# KMO_IO_MV2_9.net
KiCad netlist of a schematic drawn in EAGLE
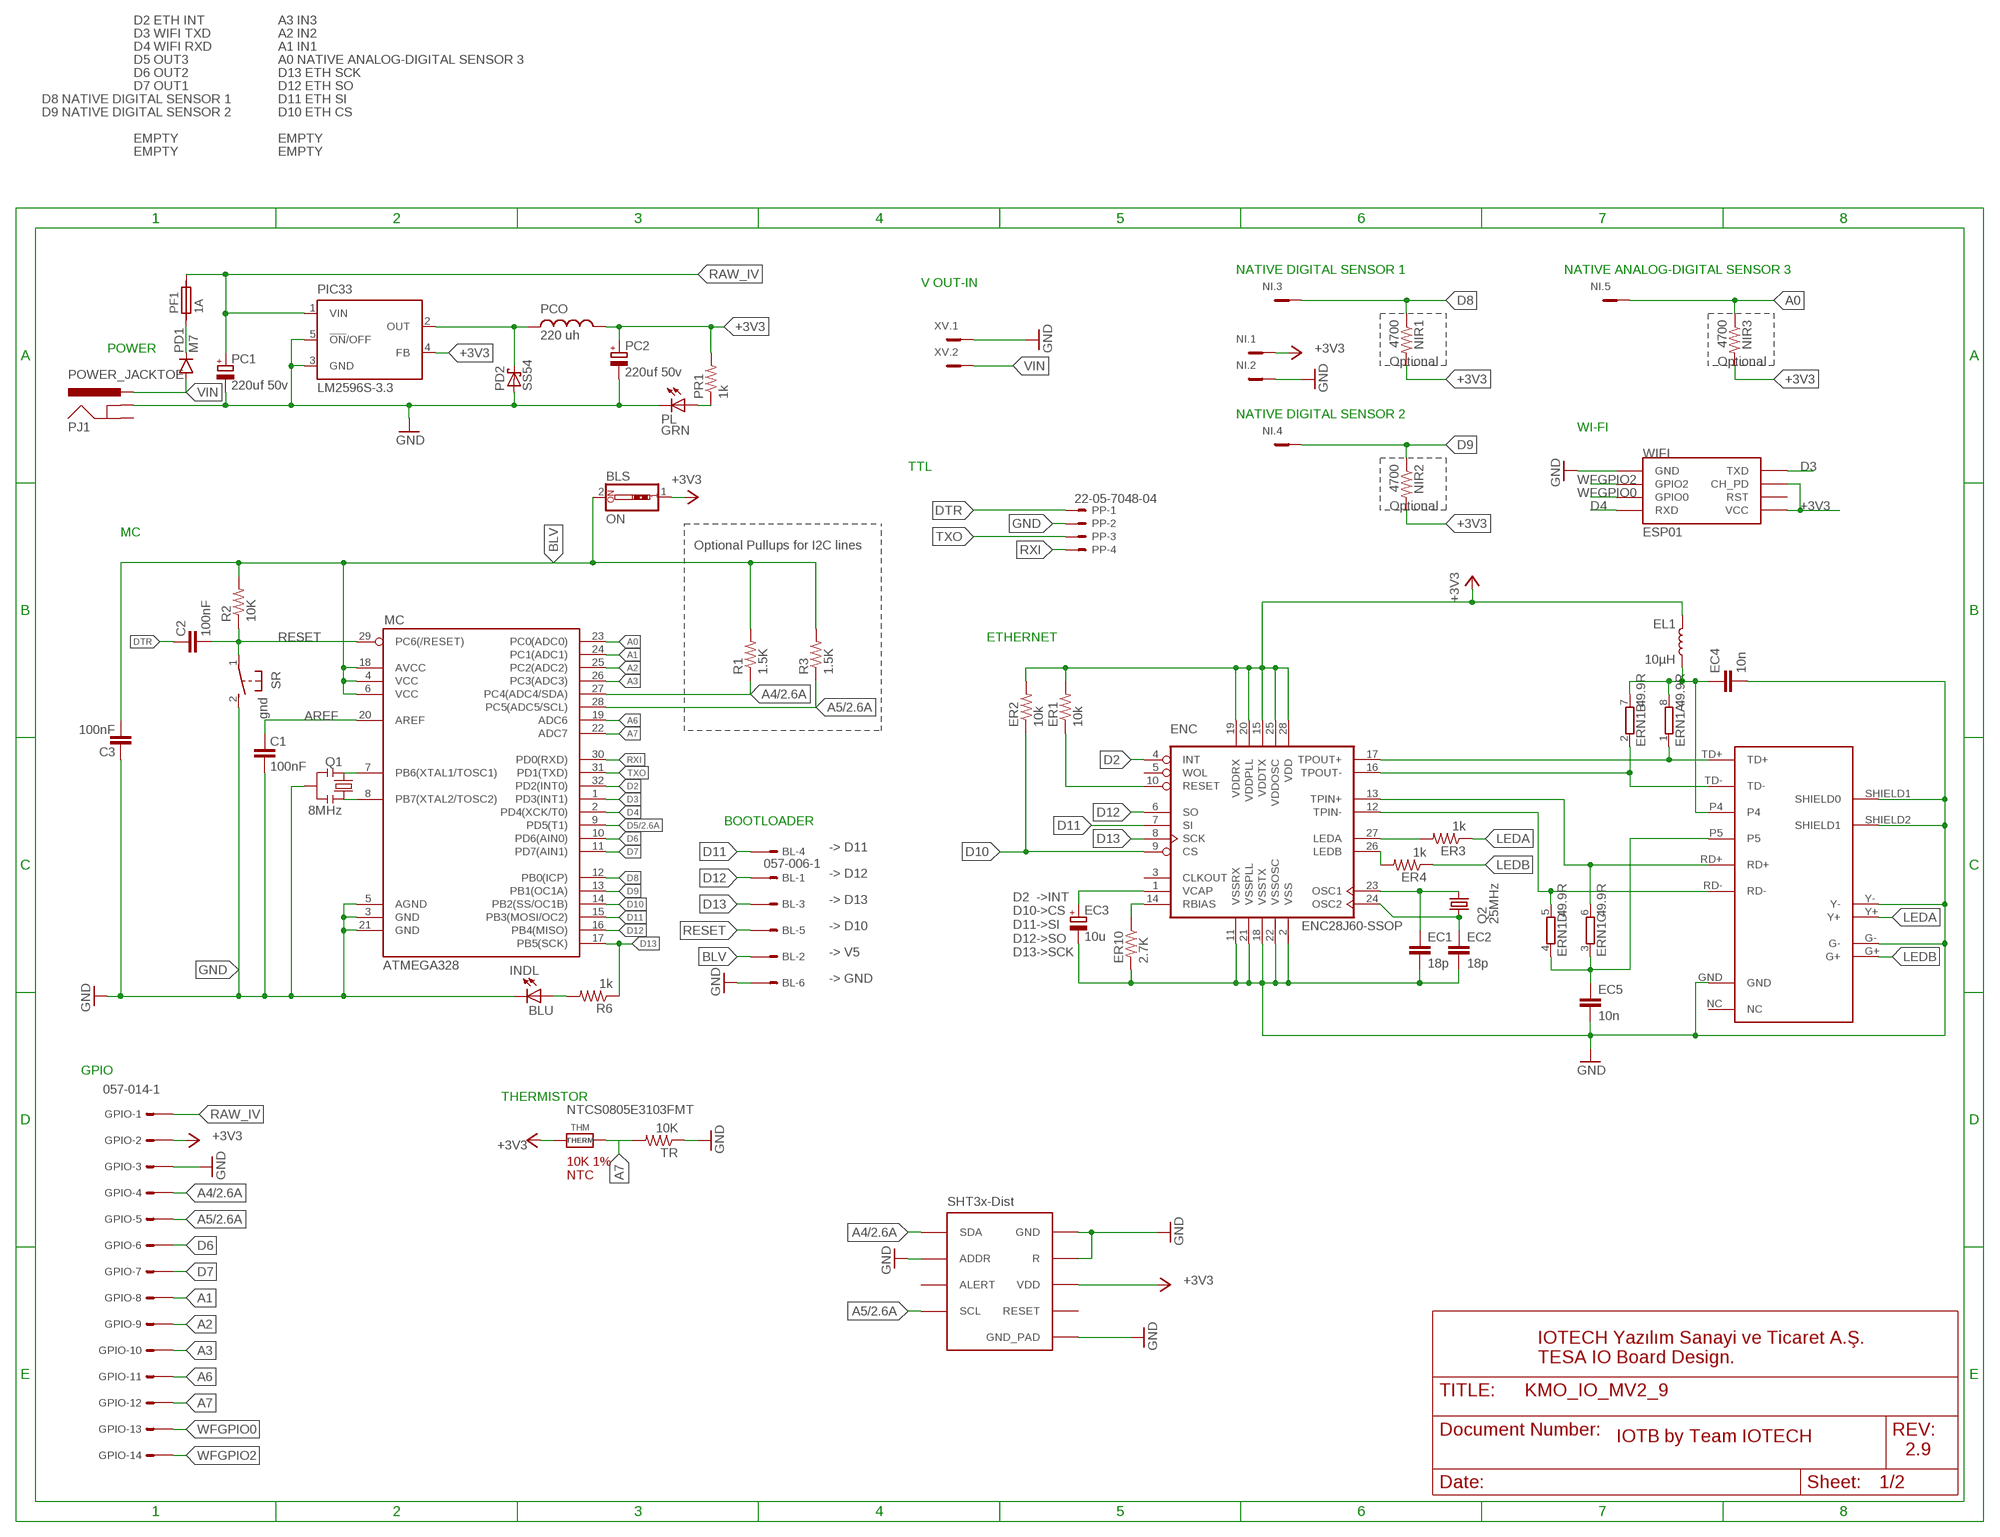
[diagram p0: schematic, sheet 1]
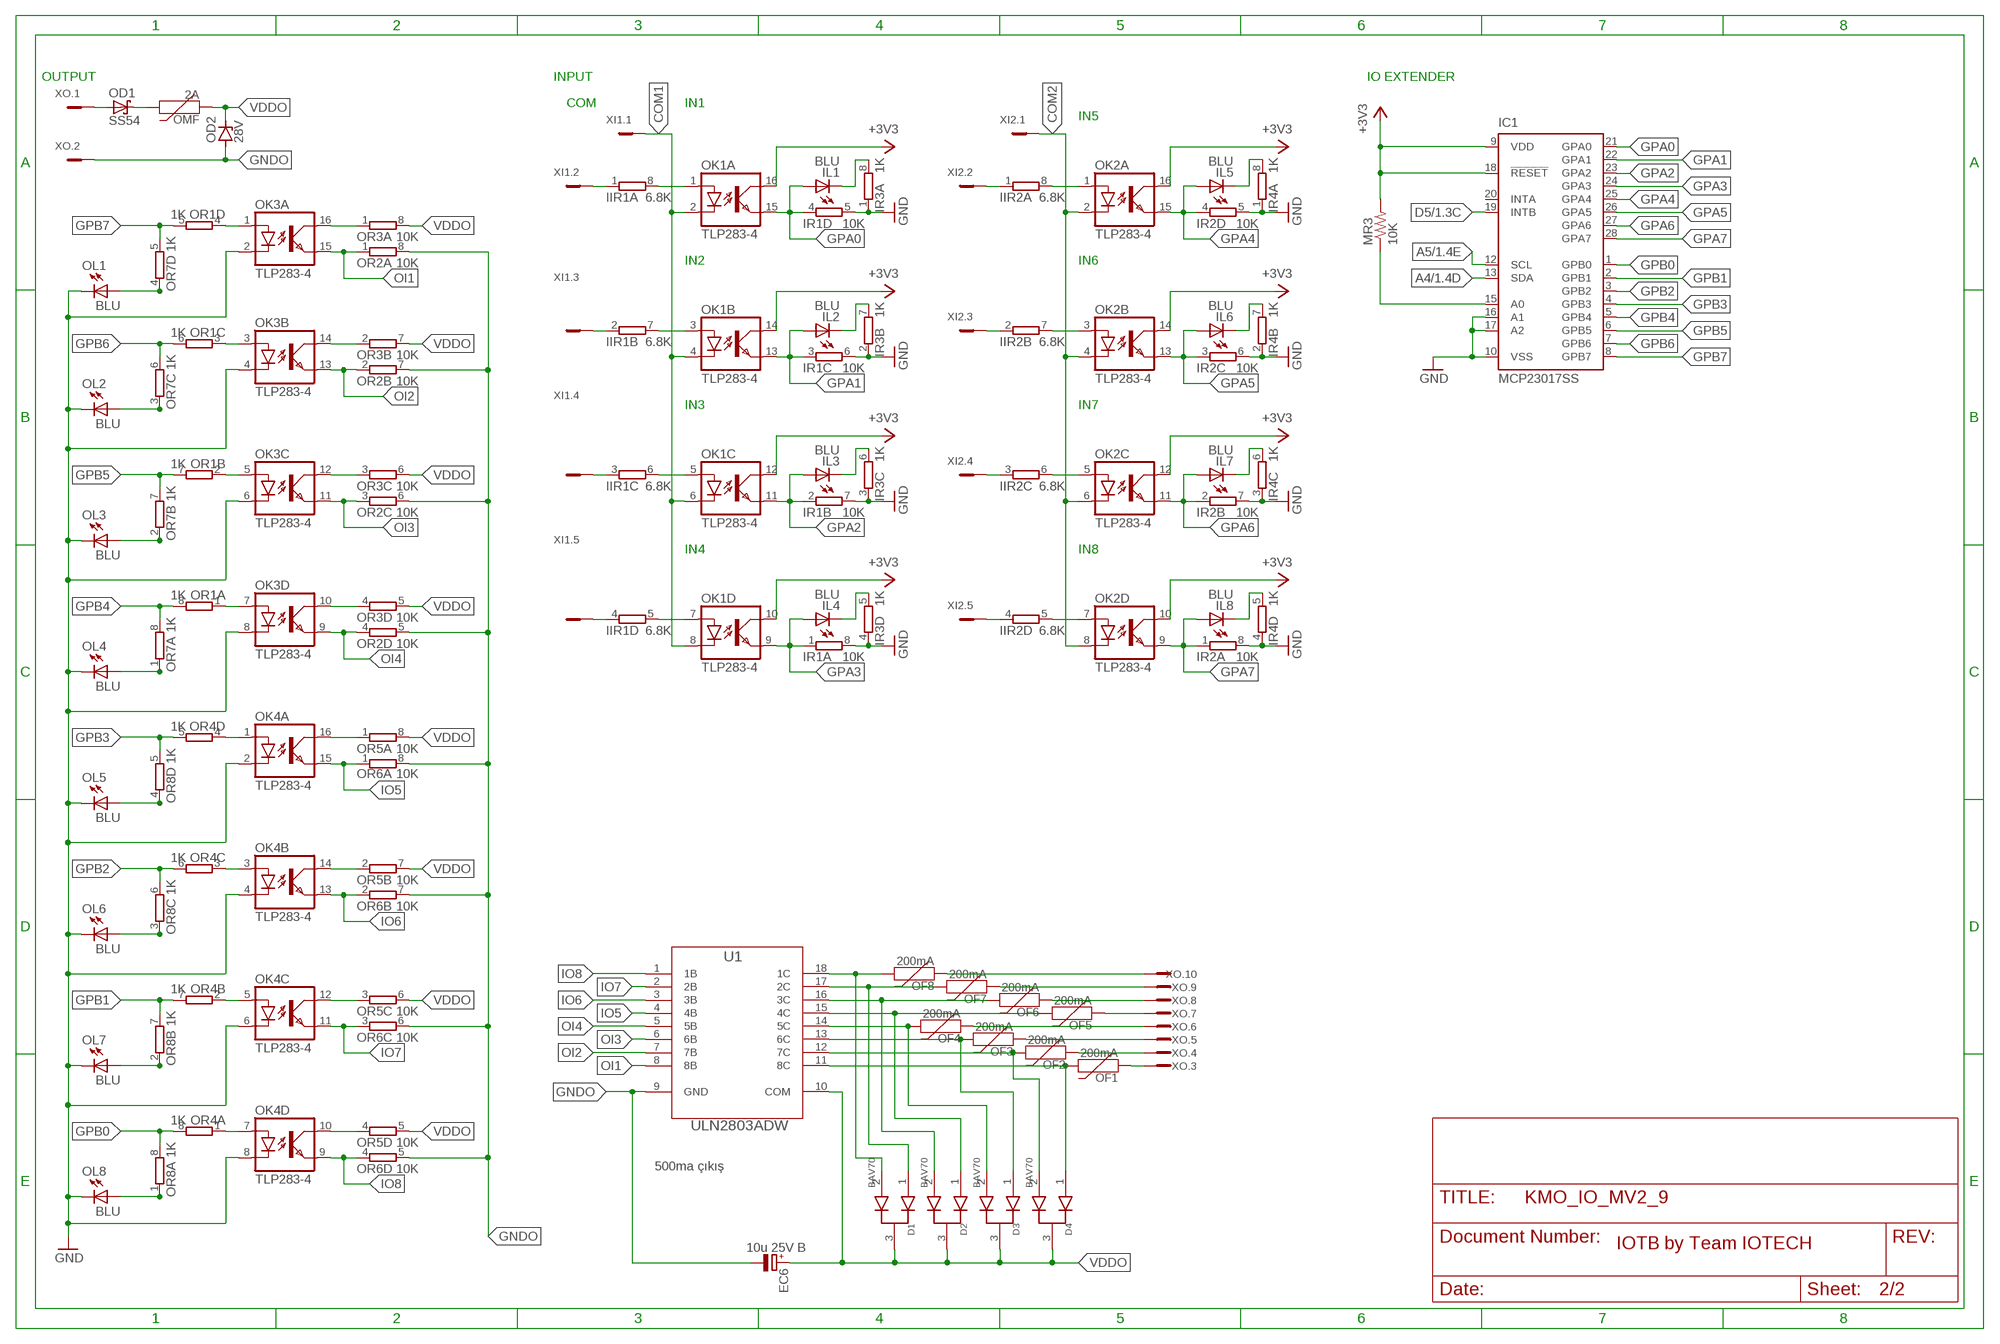
[diagram p1: schematic, sheet 2]

(export (version "E")
  (design (tool "Eeschema 10.0.6"))
  (components
    (comp (ref "D1")
      (value "BAV70")
      (footprint "eagle-import:SOT-23-3")
      (fields (field (name "MF") "Multicomp") (field (name "MP") "BAV70+"))
      (libsource (lib "eagle-import") (part "BAV70"))
    )
    (comp (ref "D2")
      (value "BAV70")
      (footprint "eagle-import:SOT-23-3")
      (fields (field (name "MF") "Multicomp") (field (name "MP") "BAV70+"))
      (libsource (lib "eagle-import") (part "BAV70"))
    )
    (comp (ref "D3")
      (value "BAV70")
      (footprint "eagle-import:SOT-23-3")
      (fields (field (name "MF") "Multicomp") (field (name "MP") "BAV70+"))
      (libsource (lib "eagle-import") (part "BAV70"))
    )
    (comp (ref "D4")
      (value "BAV70")
      (footprint "eagle-import:SOT-23-3")
      (fields (field (name "MF") "Multicomp") (field (name "MP") "BAV70+"))
      (libsource (lib "eagle-import") (part "BAV70"))
    )
    (comp (ref "EC6")
      (value "10u 25V B")
      (footprint "eagle-import:SMC_B")
      (libsource (lib "eagle-import") (part "CPOL-EUSMCB"))
    )
    (comp (ref "IC1")
      (value "MCP23017SS")
      (footprint "eagle-import:SSOP28")
      (fields (field (name "MF") "MICROCHIP") (field (name "MPN") "MCP23017-E/SS"))
      (libsource (lib "eagle-import") (part "MCP23017SS"))
    )
    (comp (ref "IIR1")
      (value "6.8K")
      (footprint "eagle-import:0603-ARV")
      (libsource (lib "eagle-import") (part "4R-N0603-ARV"))
    )
    (comp (ref "IIR2")
      (value "6.8K")
      (footprint "eagle-import:0603-ARV")
      (libsource (lib "eagle-import") (part "4R-N0603-ARV"))
    )
    (comp (ref "IL1")
      (value "BLU")
      (footprint "eagle-import:CHIP-LED0805")
      (libsource (lib "eagle-import") (part "LEDCHIP-LED0805"))
    )
    (comp (ref "IL2")
      (value "BLU")
      (footprint "eagle-import:CHIP-LED0805")
      (libsource (lib "eagle-import") (part "LEDCHIP-LED0805"))
    )
    (comp (ref "IL3")
      (value "BLU")
      (footprint "eagle-import:CHIP-LED0805")
      (libsource (lib "eagle-import") (part "LEDCHIP-LED0805"))
    )
    (comp (ref "IL4")
      (value "BLU")
      (footprint "eagle-import:CHIP-LED0805")
      (libsource (lib "eagle-import") (part "LEDCHIP-LED0805"))
    )
    (comp (ref "IL5")
      (value "BLU")
      (footprint "eagle-import:CHIP-LED0805")
      (libsource (lib "eagle-import") (part "LEDCHIP-LED0805"))
    )
    (comp (ref "IL6")
      (value "BLU")
      (footprint "eagle-import:CHIP-LED0805")
      (libsource (lib "eagle-import") (part "LEDCHIP-LED0805"))
    )
    (comp (ref "IL7")
      (value "BLU")
      (footprint "eagle-import:CHIP-LED0805")
      (libsource (lib "eagle-import") (part "LEDCHIP-LED0805"))
    )
    (comp (ref "IL8")
      (value "BLU")
      (footprint "eagle-import:CHIP-LED0805")
      (libsource (lib "eagle-import") (part "LEDCHIP-LED0805"))
    )
    (comp (ref "IR1")
      (value "10K")
      (footprint "eagle-import:0603-ARV")
      (libsource (lib "eagle-import") (part "4R-N0603-ARV"))
    )
    (comp (ref "IR2")
      (value "10K")
      (footprint "eagle-import:0603-ARV")
      (libsource (lib "eagle-import") (part "4R-N0603-ARV"))
    )
    (comp (ref "IR3")
      (value "1K")
      (footprint "eagle-import:0603-ARV")
      (libsource (lib "eagle-import") (part "4R-N0603-ARV"))
    )
    (comp (ref "IR4")
      (value "1K")
      (footprint "eagle-import:0603-ARV")
      (libsource (lib "eagle-import") (part "4R-N0603-ARV"))
    )
    (comp (ref "MR3")
      (value "10K")
      (footprint "eagle-import:0805")
      (libsource (lib "eagle-import") (part "RESISTOR0805-RES"))
    )
    (comp (ref "OD1")
      (value "SS54")
      (footprint "eagle-import:SMB")
      (libsource (lib "eagle-import") (part "SCHOTTKY-DIODESMD"))
    )
    (comp (ref "OD2")
      (value "28V")
      (footprint "eagle-import:SMB")
      (libsource (lib "eagle-import") (part "ZENER-DIODESMB"))
    )
    (comp (ref "OF1")
      (value "200mA")
      (footprint "eagle-import:1206")
      (libsource (lib "eagle-import") (part "PPTC_0.75A"))
    )
    (comp (ref "OF2")
      (value "200mA")
      (footprint "eagle-import:1206")
      (libsource (lib "eagle-import") (part "PPTC_0.75A"))
    )
    (comp (ref "OF3")
      (value "200mA")
      (footprint "eagle-import:1206")
      (libsource (lib "eagle-import") (part "PPTC_0.75A"))
    )
    (comp (ref "OF4")
      (value "200mA")
      (footprint "eagle-import:1206")
      (libsource (lib "eagle-import") (part "PPTC_0.75A"))
    )
    (comp (ref "OF5")
      (value "200mA")
      (footprint "eagle-import:1206")
      (libsource (lib "eagle-import") (part "PPTC_0.75A"))
    )
    (comp (ref "OF6")
      (value "200mA")
      (footprint "eagle-import:1206")
      (libsource (lib "eagle-import") (part "PPTC_0.75A"))
    )
    (comp (ref "OF7")
      (value "200mA")
      (footprint "eagle-import:1206")
      (libsource (lib "eagle-import") (part "PPTC_0.75A"))
    )
    (comp (ref "OF8")
      (value "200mA")
      (footprint "eagle-import:1206")
      (libsource (lib "eagle-import") (part "PPTC_0.75A"))
    )
    (comp (ref "OK1")
      (value "TLP283-4")
      (footprint "eagle-import:MINI-FLAT-16")
      (fields (field (name "SPICEPREFIX") "O"))
      (libsource (lib "eagle-import") (part "TLP283-4"))
    )
    (comp (ref "OK2")
      (value "TLP283-4")
      (footprint "eagle-import:MINI-FLAT-16")
      (fields (field (name "SPICEPREFIX") "O"))
      (libsource (lib "eagle-import") (part "TLP283-4"))
    )
    (comp (ref "OK3")
      (value "TLP283-4")
      (footprint "eagle-import:MINI-FLAT-16")
      (libsource (lib "eagle-import") (part "TLP283-4"))
    )
    (comp (ref "OK4")
      (value "TLP283-4")
      (footprint "eagle-import:MINI-FLAT-16")
      (libsource (lib "eagle-import") (part "TLP283-4"))
    )
    (comp (ref "OL1")
      (value "BLU")
      (footprint "eagle-import:CHIP-LED0805")
      (libsource (lib "eagle-import") (part "LEDCHIP-LED0805"))
    )
    (comp (ref "OL2")
      (value "BLU")
      (footprint "eagle-import:CHIP-LED0805")
      (libsource (lib "eagle-import") (part "LEDCHIP-LED0805"))
    )
    (comp (ref "OL3")
      (value "BLU")
      (footprint "eagle-import:CHIP-LED0805")
      (libsource (lib "eagle-import") (part "LEDCHIP-LED0805"))
    )
    (comp (ref "OL4")
      (value "BLU")
      (footprint "eagle-import:CHIP-LED0805")
      (libsource (lib "eagle-import") (part "LEDCHIP-LED0805"))
    )
    (comp (ref "OL5")
      (value "BLU")
      (footprint "eagle-import:CHIP-LED0805")
      (libsource (lib "eagle-import") (part "LEDCHIP-LED0805"))
    )
    (comp (ref "OL6")
      (value "BLU")
      (footprint "eagle-import:CHIP-LED0805")
      (libsource (lib "eagle-import") (part "LEDCHIP-LED0805"))
    )
    (comp (ref "OL7")
      (value "BLU")
      (footprint "eagle-import:CHIP-LED0805")
      (libsource (lib "eagle-import") (part "LEDCHIP-LED0805"))
    )
    (comp (ref "OL8")
      (value "BLU")
      (footprint "eagle-import:CHIP-LED0805")
      (libsource (lib "eagle-import") (part "LEDCHIP-LED0805"))
    )
    (comp (ref "OMF")
      (value "2A")
      (footprint "eagle-import:1206")
      (libsource (lib "eagle-import") (part "PPTC_0.75A"))
    )
    (comp (ref "OR1")
      (value "1K")
      (footprint "eagle-import:0603-ARV")
      (libsource (lib "eagle-import") (part "4R-N0603-ARV"))
    )
    (comp (ref "OR2")
      (value "10K")
      (footprint "eagle-import:0603-ARV")
      (libsource (lib "eagle-import") (part "4R-N0603-ARV"))
    )
    (comp (ref "OR3")
      (value "10K")
      (footprint "eagle-import:0603-ARV")
      (libsource (lib "eagle-import") (part "4R-N0603-ARV"))
    )
    (comp (ref "OR4")
      (value "1K")
      (footprint "eagle-import:0603-ARV")
      (libsource (lib "eagle-import") (part "4R-N0603-ARV"))
    )
    (comp (ref "OR5")
      (value "10K")
      (footprint "eagle-import:0603-ARV")
      (libsource (lib "eagle-import") (part "4R-N0603-ARV"))
    )
    (comp (ref "OR6")
      (value "10K")
      (footprint "eagle-import:0603-ARV")
      (libsource (lib "eagle-import") (part "4R-N0603-ARV"))
    )
    (comp (ref "OR7")
      (value "1K")
      (footprint "eagle-import:0603-ARV")
      (libsource (lib "eagle-import") (part "4R-N0603-ARV"))
    )
    (comp (ref "OR8")
      (value "1K")
      (footprint "eagle-import:0603-ARV")
      (libsource (lib "eagle-import") (part "4R-N0603-ARV"))
    )
    (comp (ref "U1")
      (value "ULN2803ADW")
      (footprint "eagle-import:SOIC127P1030X265-18N")
      (libsource (lib "eagle-import") (part "ULN2803ADW"))
    )
    (comp (ref "XI1")
      (value "MC5")
      (footprint "eagle-import:MC5")
      (libsource (lib "eagle-import") (part "MC5"))
    )
    (comp (ref "XI2")
      (value "MC5")
      (footprint "eagle-import:MC5")
      (libsource (lib "eagle-import") (part "MC5"))
    )
    (comp (ref "XO")
      (value "MC10")
      (footprint "eagle-import:MC10")
      (libsource (lib "eagle-import") (part "MC10"))
    )
    (comp (ref "BL")
      (value "057-006-1")
      (footprint "eagle-import:057-006-1")
      (libsource (lib "eagle-import") (part "057-006-1"))
    )
    (comp (ref "BLS")
      (value "ON")
      (footprint "eagle-import:EDG-01")
      (libsource (lib "eagle-import") (part "SW_DIP-1"))
    )
    (comp (ref "C1")
      (value "100nF")
      (footprint "eagle-import:0805")
      (libsource (lib "eagle-import") (part "CAP0805"))
    )
    (comp (ref "C2")
      (value "100nF")
      (footprint "eagle-import:0805")
      (libsource (lib "eagle-import") (part "CAP0805"))
    )
    (comp (ref "C3")
      (value "100nF")
      (footprint "eagle-import:0805")
      (libsource (lib "eagle-import") (part "CAP0805"))
    )
    (comp (ref "EC1")
      (value "18p")
      (footprint "eagle-import:0805")
      (libsource (lib "eagle-import") (part "CAP0805"))
    )
    (comp (ref "EC2")
      (value "18p")
      (footprint "eagle-import:0805")
      (libsource (lib "eagle-import") (part "CAP0805"))
    )
    (comp (ref "EC3")
      (value "10u")
      (footprint "eagle-import:CT3216")
      (libsource (lib "eagle-import") (part "CPOL-EUCT3216"))
    )
    (comp (ref "EC4")
      (value "10n")
      (footprint "eagle-import:0805")
      (libsource (lib "eagle-import") (part "CAP0805"))
    )
    (comp (ref "EC5")
      (value "10n")
      (footprint "eagle-import:0805")
      (libsource (lib "eagle-import") (part "CAP0805"))
    )
    (comp (ref "EL1")
      (value "10µH")
      (footprint "eagle-import:0805")
      (libsource (lib "eagle-import") (part "INDUCTOR-0805-3.3UH"))
    )
    (comp (ref "ENC")
      (value "ENC28J60-SSOP")
      (footprint "eagle-import:SSOP28")
      (libsource (lib "eagle-import") (part "ENC28J60-SSOP"))
    )
    (comp (ref "ER1")
      (value "10k")
      (footprint "eagle-import:0805")
      (libsource (lib "eagle-import") (part "RESISTOR0805-RES"))
    )
    (comp (ref "ER2")
      (value "10k")
      (footprint "eagle-import:0805")
      (libsource (lib "eagle-import") (part "RESISTOR0805-RES"))
    )
    (comp (ref "ER3")
      (value "1k")
      (footprint "eagle-import:0805")
      (libsource (lib "eagle-import") (part "RESISTOR0805-RES"))
    )
    (comp (ref "ER4")
      (value "1k")
      (footprint "eagle-import:0805")
      (libsource (lib "eagle-import") (part "RESISTOR0805-RES"))
    )
    (comp (ref "ER10")
      (value "2.7K")
      (footprint "eagle-import:0805")
      (libsource (lib "eagle-import") (part "RESISTOR0805-RES"))
    )
    (comp (ref "ERN1")
      (value "49.9R")
      (footprint "eagle-import:0603-ARV")
      (libsource (lib "eagle-import") (part "4R-N0603-ARV"))
    )
    (comp (ref "GPIO")
      (value "057-014-1")
      (footprint "eagle-import:057-014-1")
      (libsource (lib "eagle-import") (part "057-014-1"))
    )
    (comp (ref "INDL")
      (value "BLU")
      (footprint "eagle-import:CHIP-LED0805")
      (libsource (lib "eagle-import") (part "LEDCHIP-LED0805"))
    )
    (comp (ref "MC")
      (value "ATMEGA328")
      (footprint "eagle-import:TQFP32-08")
      (libsource (lib "eagle-import") (part "ATMEGA168"))
    )
    (comp (ref "NI")
      (value "MC5")
      (footprint "eagle-import:MC5")
      (libsource (lib "eagle-import") (part "MC5"))
    )
    (comp (ref "NIR1")
      (value "4700")
      (footprint "eagle-import:0805")
      (libsource (lib "eagle-import") (part "RESISTOR0805-RES"))
    )
    (comp (ref "NIR2")
      (value "4700")
      (footprint "eagle-import:0805")
      (libsource (lib "eagle-import") (part "RESISTOR0805-RES"))
    )
    (comp (ref "NIR3")
      (value "4700")
      (footprint "eagle-import:0805")
      (libsource (lib "eagle-import") (part "RESISTOR0805-RES"))
    )
    (comp (ref "PC1")
      (value "220uf 50v")
      (footprint "eagle-import:140CLH-1010")
      (libsource (lib "eagle-import") (part "CPOL-EU140CLH-1010"))
    )
    (comp (ref "PC2")
      (value "220uf 50v")
      (footprint "eagle-import:140CLH-1010")
      (libsource (lib "eagle-import") (part "CPOL-EU140CLH-1010"))
    )
    (comp (ref "PCO")
      (value "220 uh")
      (footprint "eagle-import:MSS1260")
      (libsource (lib "eagle-import") (part "MSS1260"))
    )
    (comp (ref "PD1")
      (value "M7")
      (footprint "eagle-import:SMA-DIODE")
      (libsource (lib "eagle-import") (part "DIODESMA"))
    )
    (comp (ref "PD2")
      (value "SS54")
      (footprint "eagle-import:SMB")
      (libsource (lib "eagle-import") (part "SCHOTTKY-DIODESMD"))
    )
    (comp (ref "PF1")
      (value "1A")
      (footprint "eagle-import:1820")
      (libsource (lib "eagle-import") (part "SIBA194600"))
    )
    (comp (ref "PIC33")
      (value "LM2596S-3.3")
      (footprint "eagle-import:TO263-5")
      (fields
        (field (name "MF") "NATIONAL SEMICONDUCTOR")
        (field (name "MPN") "LM2596S-ADJ/NOPB")
        (field (name "SPICEPREFIX") "X")
      )
      (libsource (lib "eagle-import") (part "LM2596S"))
    )
    (comp (ref "PJ1")
      (value "POWER_JACKTOE")
      (footprint "eagle-import:POWER_JACK_SMD_OVERPASTE_TOE")
      (libsource (lib "eagle-import") (part "POWER_JACKTOE"))
    )
    (comp (ref "PL")
      (value "GRN")
      (footprint "eagle-import:CHIP-LED0805")
      (libsource (lib "eagle-import") (part "LEDCHIP-LED0805"))
    )
    (comp (ref "PP")
      (value "22-05-7048-04")
      (footprint "eagle-import:7395-04")
      (fields (field (name "MF") "MOLEX"))
      (libsource (lib "eagle-import") (part "22-?-0405-7048"))
    )
    (comp (ref "PR1")
      (value "1k")
      (footprint "eagle-import:0805")
      (libsource (lib "eagle-import") (part "RESISTOR0805-RES"))
    )
    (comp (ref "Q1")
      (value "8MHz")
      (footprint "eagle-import:RESONATOR-SMD-1_1")
      (libsource (lib "eagle-import") (part "RESONATOR1{colon}1"))
    )
    (comp (ref "Q2")
      (value "25MHz")
      (footprint "eagle-import:5.0X3.2_2")
      (libsource (lib "eagle-import") (part "KX-9B"))
    )
    (comp (ref "R1")
      (value "1.5K")
      (footprint "eagle-import:0805")
      (libsource (lib "eagle-import") (part "RESISTOR0805-RES"))
    )
    (comp (ref "R2")
      (value "10K")
      (footprint "eagle-import:0805")
      (libsource (lib "eagle-import") (part "RESISTOR0805-RES"))
    )
    (comp (ref "R3")
      (value "1.5K")
      (footprint "eagle-import:0805")
      (libsource (lib "eagle-import") (part "RESISTOR0805-RES"))
    )
    (comp (ref "R6")
      (value "1k")
      (footprint "eagle-import:0805")
      (libsource (lib "eagle-import") (part "RESISTOR0805-RES"))
    )
    (comp (ref "SHT")
      (value "SHT3X")
      (footprint "eagle-import:SHT3X")
      (libsource (lib "eagle-import") (part "SHT3X"))
    )
    (comp (ref "SR")
      (value "gnd")
      (footprint "eagle-import:B3F-31XX")
      (fields (field (name "MPN") "B3F-3100"))
      (libsource (lib "eagle-import") (part "31-XX"))
    )
    (comp (ref "THM")
      (value "THERM")
      (footprint "eagle-import:MICROBUILDER_0805_NOTHERMALS")
      (libsource (lib "eagle-import") (part "MICROBUILDER_RESISTOR0805_NOTHERMALS"))
    )
    (comp (ref "TR")
      (value "10K")
      (footprint "eagle-import:0805")
      (libsource (lib "eagle-import") (part "RESISTOR0805-RES"))
    )
    (comp (ref "U$2")
      (value "HR911105A")
      (footprint "eagle-import:RJ45")
      (libsource (lib "eagle-import") (part "HR911105A"))
    )
    (comp (ref "WIFI")
      (value "ESP01")
      (footprint "eagle-import:ESP01")
      (libsource (lib "eagle-import") (part "ESP01"))
    )
    (comp (ref "XV")
      (value "MC2")
      (footprint "eagle-import:MC2")
      (libsource (lib "eagle-import") (part "MC2"))
    )
  )
  (nets
    (net (code "1") (name "+3V3") (class "Default")
      (node (ref "BLS") (pin "1") (pinfunction "1_1") (pintype "passive"))
      (node (ref "EL1") (pin "1") (pinfunction "1_1") (pintype "passive"))
      (node (ref "ENC") (pin "15") (pinfunction "VDDTX_15") (pintype "power_in"))
      (node (ref "ENC") (pin "19") (pinfunction "VDDRX_19") (pintype "power_in"))
      (node (ref "ENC") (pin "20") (pinfunction "VDDPLL_20") (pintype "power_in"))
      (node (ref "ENC") (pin "25") (pinfunction "VDDOSC_25") (pintype "power_in"))
      (node (ref "ENC") (pin "28") (pinfunction "VDD_28") (pintype "power_in"))
      (node (ref "ER1") (pin "2") (pinfunction "2_2") (pintype "passive"))
      (node (ref "ER2") (pin "2") (pinfunction "2_2") (pintype "passive"))
      (node (ref "GPIO") (pin "2") (pinfunction "S_2") (pintype "passive"))
      (node (ref "IC1") (pin "18") (pinfunction "~{RESET}_18") (pintype "input"))
      (node (ref "IC1") (pin "9") (pinfunction "VDD_9") (pintype "power_in"))
      (node (ref "MR3") (pin "2") (pinfunction "2_2") (pintype "passive"))
      (node (ref "NI") (pin "1") (pinfunction "SK_1") (pintype "passive"))
      (node (ref "NIR1") (pin "2") (pinfunction "2_2") (pintype "passive"))
      (node (ref "NIR2") (pin "2") (pinfunction "2_2") (pintype "passive"))
      (node (ref "NIR3") (pin "2") (pinfunction "2_2") (pintype "passive"))
      (node (ref "OK1") (pin "10") (pinfunction "COL_10") (pintype "passive"))
      (node (ref "OK1") (pin "12") (pinfunction "COL_12") (pintype "passive"))
      (node (ref "OK1") (pin "14") (pinfunction "COL_14") (pintype "passive"))
      (node (ref "OK1") (pin "16") (pinfunction "COL_16") (pintype "passive"))
      (node (ref "OK2") (pin "10") (pinfunction "COL_10") (pintype "passive"))
      (node (ref "OK2") (pin "12") (pinfunction "COL_12") (pintype "passive"))
      (node (ref "OK2") (pin "14") (pinfunction "COL_14") (pintype "passive"))
      (node (ref "OK2") (pin "16") (pinfunction "COL_16") (pintype "passive"))
      (node (ref "PC2") (pin "+") (pinfunction "+_+") (pintype "passive"))
      (node (ref "PCO") (pin "P$1") (pinfunction "P$1_P$1") (pintype "passive"))
      (node (ref "PIC33") (pin "4") (pinfunction "FB_4") (pintype "input"))
      (node (ref "PR1") (pin "2") (pinfunction "2_2") (pintype "passive"))
      (node (ref "SHT") (pin "VDD") (pinfunction "VDD_VDD") (pintype "bidirectional"))
      (node (ref "THM") (pin "1") (pinfunction "1_1") (pintype "passive"))
      (node (ref "WIFI") (pin "CH_PD") (pinfunction "CH_PD_CH_PD") (pintype "bidirectional"))
      (node (ref "WIFI") (pin "VCC") (pinfunction "VCC_VCC") (pintype "bidirectional"))
    )
    (net (code "2") (name "A0") (class "Default")
      (node (ref "MC") (pin "23") (pinfunction "PC0(ADC0)_23") (pintype "bidirectional"))
      (node (ref "NI") (pin "5") (pinfunction "SK_5") (pintype "passive"))
      (node (ref "NIR3") (pin "1") (pinfunction "1_1") (pintype "passive"))
    )
    (net (code "3") (name "A1") (class "Default")
      (node (ref "GPIO") (pin "8") (pinfunction "S_8") (pintype "passive"))
      (node (ref "MC") (pin "24") (pinfunction "PC1(ADC1)_24") (pintype "bidirectional"))
    )
    (net (code "4") (name "A2") (class "Default")
      (node (ref "GPIO") (pin "9") (pinfunction "S_9") (pintype "passive"))
      (node (ref "MC") (pin "25") (pinfunction "PC2(ADC2)_25") (pintype "bidirectional"))
    )
    (net (code "5") (name "A3") (class "Default")
      (node (ref "GPIO") (pin "10") (pinfunction "S_10") (pintype "passive"))
      (node (ref "MC") (pin "26") (pinfunction "PC3(ADC3)_26") (pintype "bidirectional"))
    )
    (net (code "6") (name "A4") (class "Default")
      (node (ref "GPIO") (pin "4") (pinfunction "S_4") (pintype "passive"))
      (node (ref "IC1") (pin "13") (pinfunction "SDA_13") (pintype "bidirectional"))
      (node (ref "MC") (pin "27") (pinfunction "PC4(ADC4/SDA)_27") (pintype "bidirectional"))
      (node (ref "R1") (pin "1") (pinfunction "1_1") (pintype "passive"))
      (node (ref "SHT") (pin "SDA") (pinfunction "SDA_SDA") (pintype "bidirectional"))
    )
    (net (code "7") (name "A5") (class "Default")
      (node (ref "GPIO") (pin "5") (pinfunction "S_5") (pintype "passive"))
      (node (ref "IC1") (pin "12") (pinfunction "SCL_12") (pintype "input"))
      (node (ref "MC") (pin "28") (pinfunction "PC5(ADC5/SCL)_28") (pintype "bidirectional"))
      (node (ref "R3") (pin "1") (pinfunction "1_1") (pintype "passive"))
      (node (ref "SHT") (pin "SCL") (pinfunction "SCL_SCL") (pintype "bidirectional"))
    )
    (net (code "8") (name "A6") (class "Default")
      (node (ref "GPIO") (pin "11") (pinfunction "S_11") (pintype "passive"))
      (node (ref "MC") (pin "19") (pinfunction "ADC6_19") (pintype "bidirectional"))
    )
    (net (code "9") (name "A7") (class "Default")
      (node (ref "GPIO") (pin "12") (pinfunction "S_12") (pintype "passive"))
      (node (ref "MC") (pin "22") (pinfunction "ADC7_22") (pintype "bidirectional"))
      (node (ref "THM") (pin "2") (pinfunction "2_2") (pintype "passive"))
      (node (ref "TR") (pin "2") (pinfunction "2_2") (pintype "passive"))
    )
    (net (code "10") (name "AREF") (class "Default")
      (node (ref "C1") (pin "2") (pinfunction "2_2") (pintype "passive"))
      (node (ref "MC") (pin "20") (pinfunction "AREF_20") (pintype "bidirectional"))
    )
    (net (code "11") (name "BLV") (class "Default")
      (node (ref "BL") (pin "2") (pinfunction "S_2") (pintype "passive"))
      (node (ref "BLS") (pin "2") (pinfunction "2_2") (pintype "passive"))
      (node (ref "C3") (pin "1") (pinfunction "1_1") (pintype "passive"))
      (node (ref "MC") (pin "18") (pinfunction "AVCC_18") (pintype "bidirectional"))
      (node (ref "MC") (pin "4") (pinfunction "VCC_4") (pintype "bidirectional"))
      (node (ref "MC") (pin "6") (pinfunction "VCC_6") (pintype "bidirectional"))
      (node (ref "R1") (pin "2") (pinfunction "2_2") (pintype "passive"))
      (node (ref "R2") (pin "2") (pinfunction "2_2") (pintype "passive"))
      (node (ref "R3") (pin "2") (pinfunction "2_2") (pintype "passive"))
    )
    (net (code "12") (name "COM1") (class "Default")
      (node (ref "OK1") (pin "2") (pinfunction "C_2") (pintype "passive"))
      (node (ref "OK1") (pin "4") (pinfunction "C_4") (pintype "passive"))
      (node (ref "OK1") (pin "6") (pinfunction "C_6") (pintype "passive"))
      (node (ref "OK1") (pin "8") (pinfunction "C_8") (pintype "passive"))
      (node (ref "XI1") (pin "1") (pinfunction "SK_1") (pintype "passive"))
    )
    (net (code "13") (name "COM2") (class "Default")
      (node (ref "OK2") (pin "2") (pinfunction "C_2") (pintype "passive"))
      (node (ref "OK2") (pin "4") (pinfunction "C_4") (pintype "passive"))
      (node (ref "OK2") (pin "6") (pinfunction "C_6") (pintype "passive"))
      (node (ref "OK2") (pin "8") (pinfunction "C_8") (pintype "passive"))
      (node (ref "XI2") (pin "1") (pinfunction "SK_1") (pintype "passive"))
    )
    (net (code "14") (name "D2") (class "Default")
      (node (ref "ENC") (pin "4") (pinfunction "INT_4") (pintype "output"))
      (node (ref "MC") (pin "32") (pinfunction "PD2(INT0)_32") (pintype "bidirectional"))
    )
    (net (code "15") (name "D3") (class "Default")
      (node (ref "MC") (pin "1") (pinfunction "PD3(INT1)_1") (pintype "bidirectional"))
      (node (ref "WIFI") (pin "TX") (pinfunction "TXD_TX") (pintype "bidirectional"))
    )
    (net (code "16") (name "D4") (class "Default")
      (node (ref "MC") (pin "2") (pinfunction "PD4(XCK/T0)_2") (pintype "bidirectional"))
      (node (ref "WIFI") (pin "RX") (pinfunction "RXD_RX") (pintype "bidirectional"))
    )
    (net (code "17") (name "D5") (class "Default")
      (node (ref "IC1") (pin "19") (pinfunction "INTB_19") (pintype "output"))
      (node (ref "MC") (pin "9") (pinfunction "PD5(T1)_9") (pintype "bidirectional"))
    )
    (net (code "18") (name "D6") (class "Default")
      (node (ref "GPIO") (pin "6") (pinfunction "S_6") (pintype "passive"))
      (node (ref "MC") (pin "10") (pinfunction "PD6(AIN0)_10") (pintype "bidirectional"))
    )
    (net (code "19") (name "D7") (class "Default")
      (node (ref "GPIO") (pin "7") (pinfunction "S_7") (pintype "passive"))
      (node (ref "MC") (pin "11") (pinfunction "PD7(AIN1)_11") (pintype "bidirectional"))
    )
    (net (code "20") (name "D8") (class "Default")
      (node (ref "MC") (pin "12") (pinfunction "PB0(ICP)_12") (pintype "bidirectional"))
      (node (ref "NI") (pin "3") (pinfunction "SK_3") (pintype "passive"))
      (node (ref "NIR1") (pin "1") (pinfunction "1_1") (pintype "passive"))
    )
    (net (code "21") (name "D9") (class "Default")
      (node (ref "MC") (pin "13") (pinfunction "PB1(OC1A)_13") (pintype "bidirectional"))
      (node (ref "NI") (pin "4") (pinfunction "SK_4") (pintype "passive"))
      (node (ref "NIR2") (pin "1") (pinfunction "1_1") (pintype "passive"))
    )
    (net (code "22") (name "D10") (class "Default")
      (node (ref "ENC") (pin "9") (pinfunction "CS_9") (pintype "input"))
      (node (ref "ER2") (pin "1") (pinfunction "1_1") (pintype "passive"))
      (node (ref "MC") (pin "14") (pinfunction "PB2(SS/OC1B)_14") (pintype "bidirectional"))
    )
    (net (code "23") (name "D11") (class "Default")
      (node (ref "BL") (pin "4") (pinfunction "S_4") (pintype "passive"))
      (node (ref "ENC") (pin "7") (pinfunction "SI_7") (pintype "input"))
      (node (ref "MC") (pin "15") (pinfunction "PB3(MOSI/OC2)_15") (pintype "bidirectional"))
    )
    (net (code "24") (name "D12") (class "Default")
      (node (ref "BL") (pin "1") (pinfunction "S_1") (pintype "passive"))
      (node (ref "ENC") (pin "6") (pinfunction "SO_6") (pintype "output"))
      (node (ref "MC") (pin "16") (pinfunction "PB4(MISO)_16") (pintype "bidirectional"))
    )
    (net (code "25") (name "D13") (class "Default")
      (node (ref "BL") (pin "3") (pinfunction "S_3") (pintype "passive"))
      (node (ref "ENC") (pin "8") (pinfunction "SCK_8") (pintype "input"))
      (node (ref "MC") (pin "17") (pinfunction "PB5(SCK)_17") (pintype "bidirectional"))
      (node (ref "R6") (pin "1") (pinfunction "1_1") (pintype "passive"))
    )
    (net (code "26") (name "DTR") (class "Default")
      (node (ref "C2") (pin "2") (pinfunction "2_2") (pintype "passive"))
      (node (ref "PP") (pin "1") (pinfunction "S_1") (pintype "passive"))
    )
    (net (code "27") (name "GND") (class "Default")
      (node (ref "BL") (pin "6") (pinfunction "S_6") (pintype "passive"))
      (node (ref "C1") (pin "1") (pinfunction "1_1") (pintype "passive"))
      (node (ref "C3") (pin "2") (pinfunction "2_2") (pintype "passive"))
      (node (ref "EC1") (pin "2") (pinfunction "2_2") (pintype "passive"))
      (node (ref "EC2") (pin "2") (pinfunction "2_2") (pintype "passive"))
      (node (ref "EC3") (pin "-") (pinfunction "-_-") (pintype "passive"))
      (node (ref "EC4") (pin "2") (pinfunction "2_2") (pintype "passive"))
      (node (ref "EC5") (pin "2") (pinfunction "2_2") (pintype "passive"))
      (node (ref "ENC") (pin "11") (pinfunction "VSSRX_11") (pintype "power_in"))
      (node (ref "ENC") (pin "18") (pinfunction "VSSTX_18") (pintype "power_in"))
      (node (ref "ENC") (pin "2") (pinfunction "VSS_2") (pintype "power_in"))
      (node (ref "ENC") (pin "21") (pinfunction "VSSPLL_21") (pintype "power_in"))
      (node (ref "ENC") (pin "22") (pinfunction "VSSOSC_22") (pintype "power_in"))
      (node (ref "ER10") (pin "2") (pinfunction "2_2") (pintype "passive"))
      (node (ref "GPIO") (pin "3") (pinfunction "S_3") (pintype "passive"))
      (node (ref "IC1") (pin "10") (pinfunction "VSS_10") (pintype "power_in"))
      (node (ref "IC1") (pin "16") (pinfunction "A1_16") (pintype "input"))
      (node (ref "IC1") (pin "17") (pinfunction "A2_17") (pintype "input"))
      (node (ref "INDL") (pin "C") (pinfunction "C_C") (pintype "passive"))
      (node (ref "IR1") (pin "5") (pinfunction "2_5") (pintype "passive"))
      (node (ref "IR1") (pin "6") (pinfunction "2_6") (pintype "passive"))
      (node (ref "IR1") (pin "7") (pinfunction "2_7") (pintype "passive"))
      (node (ref "IR1") (pin "8") (pinfunction "2_8") (pintype "passive"))
      (node (ref "IR2") (pin "5") (pinfunction "2_5") (pintype "passive"))
      (node (ref "IR2") (pin "6") (pinfunction "2_6") (pintype "passive"))
      (node (ref "IR2") (pin "7") (pinfunction "2_7") (pintype "passive"))
      (node (ref "IR2") (pin "8") (pinfunction "2_8") (pintype "passive"))
      (node (ref "IR3") (pin "1") (pinfunction "1_1") (pintype "passive"))
      (node (ref "IR3") (pin "2") (pinfunction "1_2") (pintype "passive"))
      (node (ref "IR3") (pin "3") (pinfunction "1_3") (pintype "passive"))
      (node (ref "IR3") (pin "4") (pinfunction "1_4") (pintype "passive"))
      (node (ref "IR4") (pin "1") (pinfunction "1_1") (pintype "passive"))
      (node (ref "IR4") (pin "2") (pinfunction "1_2") (pintype "passive"))
      (node (ref "IR4") (pin "3") (pinfunction "1_3") (pintype "passive"))
      (node (ref "IR4") (pin "4") (pinfunction "1_4") (pintype "passive"))
      (node (ref "MC") (pin "21") (pinfunction "GND_21") (pintype "bidirectional"))
      (node (ref "MC") (pin "3") (pinfunction "GND_3") (pintype "bidirectional"))
      (node (ref "MC") (pin "5") (pinfunction "AGND_5") (pintype "bidirectional"))
      (node (ref "NI") (pin "2") (pinfunction "SK_2") (pintype "passive"))
      (node (ref "OK3") (pin "2") (pinfunction "C_2") (pintype "passive"))
      (node (ref "OK3") (pin "4") (pinfunction "C_4") (pintype "passive"))
      (node (ref "OK3") (pin "6") (pinfunction "C_6") (pintype "passive"))
      (node (ref "OK3") (pin "8") (pinfunction "C_8") (pintype "passive"))
      (node (ref "OK4") (pin "2") (pinfunction "C_2") (pintype "passive"))
      (node (ref "OK4") (pin "4") (pinfunction "C_4") (pintype "passive"))
      (node (ref "OK4") (pin "6") (pinfunction "C_6") (pintype "passive"))
      (node (ref "OK4") (pin "8") (pinfunction "C_8") (pintype "passive"))
      (node (ref "OL1") (pin "C") (pinfunction "C_C") (pintype "passive"))
      (node (ref "OL2") (pin "C") (pinfunction "C_C") (pintype "passive"))
      (node (ref "OL3") (pin "C") (pinfunction "C_C") (pintype "passive"))
      (node (ref "OL4") (pin "C") (pinfunction "C_C") (pintype "passive"))
      (node (ref "OL5") (pin "C") (pinfunction "C_C") (pintype "passive"))
      (node (ref "OL6") (pin "C") (pinfunction "C_C") (pintype "passive"))
      (node (ref "OL7") (pin "C") (pinfunction "C_C") (pintype "passive"))
      (node (ref "OL8") (pin "C") (pinfunction "C_C") (pintype "passive"))
      (node (ref "PC1") (pin "-") (pinfunction "-_-") (pintype "passive"))
      (node (ref "PC2") (pin "-") (pinfunction "-_-") (pintype "passive"))
      (node (ref "PD2") (pin "A") (pinfunction "A_A") (pintype "passive"))
      (node (ref "PIC33") (pin "3") (pinfunction "GND_3") (pintype "power_in"))
      (node (ref "PIC33") (pin "5") (pinfunction "~{ON}/OFF_5") (pintype "input"))
      (node (ref "PJ1") (pin "GND") (pinfunction "GNDBREAK_GND") (pintype "bidirectional"))
      (node (ref "PL") (pin "C") (pinfunction "C_C") (pintype "passive"))
      (node (ref "PP") (pin "2") (pinfunction "S_2") (pintype "passive"))
      (node (ref "Q1") (pin "2") (pinfunction "2_2") (pintype "passive"))
      (node (ref "SHT") (pin "ADDR") (pinfunction "ADDR_ADDR") (pintype "bidirectional"))
      (node (ref "SHT") (pin "GND") (pinfunction "GND_GND") (pintype "bidirectional"))
      (node (ref "SHT") (pin "GND_PAD") (pinfunction "GND_PAD_GND_PAD") (pintype "bidirectional"))
      (node (ref "SHT") (pin "R") (pinfunction "R_R") (pintype "bidirectional"))
      (node (ref "SR") (pin "2") (pinfunction "S_2") (pintype "passive"))
      (node (ref "TR") (pin "1") (pinfunction "1_1") (pintype "passive"))
      (node (ref "U$2") (pin "G-") (pinfunction "G-_G-") (pintype "bidirectional"))
      (node (ref "U$2") (pin "GND") (pinfunction "GND_GND") (pintype "bidirectional"))
      (node (ref "U$2") (pin "SHIELD1") (pinfunction "SHIELD0_SHIELD1") (pintype "bidirectional"))
      (node (ref "U$2") (pin "SHIELD2") (pinfunction "SHIELD1_SHIELD2") (pintype "bidirectional"))
      (node (ref "U$2") (pin "Y-") (pinfunction "Y-_Y-") (pintype "bidirectional"))
      (node (ref "WIFI") (pin "GND") (pinfunction "GND_GND") (pintype "bidirectional"))
      (node (ref "XV") (pin "1") (pinfunction "SK_1") (pintype "passive"))
    )
    (net (code "28") (name "GNDO") (class "Default")
      (node (ref "EC6") (pin "-") (pinfunction "-_-") (pintype "passive"))
      (node (ref "OD2") (pin "A") (pinfunction "A_A") (pintype "passive"))
      (node (ref "OR2") (pin "5") (pinfunction "2_5") (pintype "passive"))
      (node (ref "OR2") (pin "6") (pinfunction "2_6") (pintype "passive"))
      (node (ref "OR2") (pin "7") (pinfunction "2_7") (pintype "passive"))
      (node (ref "OR2") (pin "8") (pinfunction "2_8") (pintype "passive"))
      (node (ref "OR6") (pin "5") (pinfunction "2_5") (pintype "passive"))
      (node (ref "OR6") (pin "6") (pinfunction "2_6") (pintype "passive"))
      (node (ref "OR6") (pin "7") (pinfunction "2_7") (pintype "passive"))
      (node (ref "OR6") (pin "8") (pinfunction "2_8") (pintype "passive"))
      (node (ref "U1") (pin "9") (pinfunction "GND_9") (pintype "passive"))
      (node (ref "XO") (pin "2") (pinfunction "SK_2") (pintype "passive"))
    )
    (net (code "29") (name "GPA0") (class "Default")
      (node (ref "IC1") (pin "21") (pinfunction "GPA0_21") (pintype "bidirectional"))
      (node (ref "IL1") (pin "A") (pinfunction "A_A") (pintype "passive"))
      (node (ref "IR1") (pin "4") (pinfunction "1_4") (pintype "passive"))
      (node (ref "OK1") (pin "15") (pinfunction "EMIT_15") (pintype "passive"))
    )
    (net (code "30") (name "GPA1") (class "Default")
      (node (ref "IC1") (pin "22") (pinfunction "GPA1_22") (pintype "bidirectional"))
      (node (ref "IL2") (pin "A") (pinfunction "A_A") (pintype "passive"))
      (node (ref "IR1") (pin "3") (pinfunction "1_3") (pintype "passive"))
      (node (ref "OK1") (pin "13") (pinfunction "EMIT_13") (pintype "passive"))
    )
    (net (code "31") (name "GPA2") (class "Default")
      (node (ref "IC1") (pin "23") (pinfunction "GPA2_23") (pintype "bidirectional"))
      (node (ref "IL3") (pin "A") (pinfunction "A_A") (pintype "passive"))
      (node (ref "IR1") (pin "2") (pinfunction "1_2") (pintype "passive"))
      (node (ref "OK1") (pin "11") (pinfunction "EMIT_11") (pintype "passive"))
    )
    (net (code "32") (name "GPA3") (class "Default")
      (node (ref "IC1") (pin "24") (pinfunction "GPA3_24") (pintype "bidirectional"))
      (node (ref "IL4") (pin "A") (pinfunction "A_A") (pintype "passive"))
      (node (ref "IR1") (pin "1") (pinfunction "1_1") (pintype "passive"))
      (node (ref "OK1") (pin "9") (pinfunction "EMIT_9") (pintype "passive"))
    )
    (net (code "33") (name "GPA4") (class "Default")
      (node (ref "IC1") (pin "25") (pinfunction "GPA4_25") (pintype "bidirectional"))
      (node (ref "IL5") (pin "A") (pinfunction "A_A") (pintype "passive"))
      (node (ref "IR2") (pin "4") (pinfunction "1_4") (pintype "passive"))
      (node (ref "OK2") (pin "15") (pinfunction "EMIT_15") (pintype "passive"))
    )
    (net (code "34") (name "GPA5") (class "Default")
      (node (ref "IC1") (pin "26") (pinfunction "GPA5_26") (pintype "bidirectional"))
      (node (ref "IL6") (pin "A") (pinfunction "A_A") (pintype "passive"))
      (node (ref "IR2") (pin "3") (pinfunction "1_3") (pintype "passive"))
      (node (ref "OK2") (pin "13") (pinfunction "EMIT_13") (pintype "passive"))
    )
    (net (code "35") (name "GPA6") (class "Default")
      (node (ref "IC1") (pin "27") (pinfunction "GPA6_27") (pintype "bidirectional"))
      (node (ref "IL7") (pin "A") (pinfunction "A_A") (pintype "passive"))
      (node (ref "IR2") (pin "2") (pinfunction "1_2") (pintype "passive"))
      (node (ref "OK2") (pin "11") (pinfunction "EMIT_11") (pintype "passive"))
    )
    (net (code "36") (name "GPA7") (class "Default")
      (node (ref "IC1") (pin "28") (pinfunction "GPA7_28") (pintype "bidirectional"))
      (node (ref "IL8") (pin "A") (pinfunction "A_A") (pintype "passive"))
      (node (ref "IR2") (pin "1") (pinfunction "1_1") (pintype "passive"))
      (node (ref "OK2") (pin "9") (pinfunction "EMIT_9") (pintype "passive"))
    )
    (net (code "37") (name "GPB0") (class "Default")
      (node (ref "IC1") (pin "1") (pinfunction "GPB0_1") (pintype "bidirectional"))
      (node (ref "OR4") (pin "8") (pinfunction "2_8") (pintype "passive"))
      (node (ref "OR8") (pin "8") (pinfunction "2_8") (pintype "passive"))
    )
    (net (code "38") (name "GPB1") (class "Default")
      (node (ref "IC1") (pin "2") (pinfunction "GPB1_2") (pintype "bidirectional"))
      (node (ref "OR4") (pin "7") (pinfunction "2_7") (pintype "passive"))
      (node (ref "OR8") (pin "7") (pinfunction "2_7") (pintype "passive"))
    )
    (net (code "39") (name "GPB2") (class "Default")
      (node (ref "IC1") (pin "3") (pinfunction "GPB2_3") (pintype "bidirectional"))
      (node (ref "OR4") (pin "6") (pinfunction "2_6") (pintype "passive"))
      (node (ref "OR8") (pin "6") (pinfunction "2_6") (pintype "passive"))
    )
    (net (code "40") (name "GPB3") (class "Default")
      (node (ref "IC1") (pin "4") (pinfunction "GPB3_4") (pintype "bidirectional"))
      (node (ref "OR4") (pin "5") (pinfunction "2_5") (pintype "passive"))
      (node (ref "OR8") (pin "5") (pinfunction "2_5") (pintype "passive"))
    )
    (net (code "41") (name "GPB4") (class "Default")
      (node (ref "IC1") (pin "5") (pinfunction "GPB4_5") (pintype "bidirectional"))
      (node (ref "OR1") (pin "8") (pinfunction "2_8") (pintype "passive"))
      (node (ref "OR7") (pin "8") (pinfunction "2_8") (pintype "passive"))
    )
    (net (code "42") (name "GPB5") (class "Default")
      (node (ref "IC1") (pin "6") (pinfunction "GPB5_6") (pintype "bidirectional"))
      (node (ref "OR1") (pin "7") (pinfunction "2_7") (pintype "passive"))
      (node (ref "OR7") (pin "7") (pinfunction "2_7") (pintype "passive"))
    )
    (net (code "43") (name "GPB6") (class "Default")
      (node (ref "IC1") (pin "7") (pinfunction "GPB6_7") (pintype "bidirectional"))
      (node (ref "OR1") (pin "6") (pinfunction "2_6") (pintype "passive"))
      (node (ref "OR7") (pin "6") (pinfunction "2_6") (pintype "passive"))
    )
    (net (code "44") (name "GPB7") (class "Default")
      (node (ref "IC1") (pin "8") (pinfunction "GPB7_8") (pintype "bidirectional"))
      (node (ref "OR1") (pin "5") (pinfunction "2_5") (pintype "passive"))
      (node (ref "OR7") (pin "5") (pinfunction "2_5") (pintype "passive"))
    )
    (net (code "45") (name "IO5") (class "Default")
      (node (ref "OK4") (pin "15") (pinfunction "EMIT_15") (pintype "passive"))
      (node (ref "OR6") (pin "1") (pinfunction "1_1") (pintype "passive"))
      (node (ref "U1") (pin "4") (pinfunction "4B_4") (pintype "input"))
    )
    (net (code "46") (name "IO6") (class "Default")
      (node (ref "OK4") (pin "13") (pinfunction "EMIT_13") (pintype "passive"))
      (node (ref "OR6") (pin "2") (pinfunction "1_2") (pintype "passive"))
      (node (ref "U1") (pin "3") (pinfunction "3B_3") (pintype "input"))
    )
    (net (code "47") (name "IO7") (class "Default")
      (node (ref "OK4") (pin "11") (pinfunction "EMIT_11") (pintype "passive"))
      (node (ref "OR6") (pin "3") (pinfunction "1_3") (pintype "passive"))
      (node (ref "U1") (pin "2") (pinfunction "2B_2") (pintype "input"))
    )
    (net (code "48") (name "IO8") (class "Default")
      (node (ref "OK4") (pin "9") (pinfunction "EMIT_9") (pintype "passive"))
      (node (ref "OR6") (pin "4") (pinfunction "1_4") (pintype "passive"))
      (node (ref "U1") (pin "1") (pinfunction "1B_1") (pintype "input"))
    )
    (net (code "49") (name "LEDA") (class "Default")
      (node (ref "ER3") (pin "1") (pinfunction "1_1") (pintype "passive"))
      (node (ref "U$2") (pin "Y+") (pinfunction "Y+_Y+") (pintype "bidirectional"))
    )
    (net (code "50") (name "LEDB") (class "Default")
      (node (ref "ER4") (pin "1") (pinfunction "1_1") (pintype "passive"))
      (node (ref "U$2") (pin "G+") (pinfunction "G+_G+") (pintype "bidirectional"))
    )
    (net (code "51") (name "Net-(ENC-LEDA)") (class "Default")
      (node (ref "ENC") (pin "27") (pinfunction "LEDA_27") (pintype "output"))
      (node (ref "ER3") (pin "2") (pinfunction "2_2") (pintype "passive"))
    )
    (net (code "52") (name "Net-(ENC-LEDB)") (class "Default")
      (node (ref "ENC") (pin "26") (pinfunction "LEDB_26") (pintype "output"))
      (node (ref "ER4") (pin "2") (pinfunction "2_2") (pintype "passive"))
    )
    (net (code "53") (name "Net-(ENC-OSC1)") (class "Default")
      (node (ref "EC1") (pin "1") (pinfunction "1_1") (pintype "passive"))
      (node (ref "ENC") (pin "23") (pinfunction "OSC1_23") (pintype "input"))
      (node (ref "Q2") (pin "2") (pinfunction "2_2") (pintype "passive"))
    )
    (net (code "54") (name "Net-(ENC-OSC2)") (class "Default")
      (node (ref "EC2") (pin "1") (pinfunction "1_1") (pintype "passive"))
      (node (ref "ENC") (pin "24") (pinfunction "OSC2_24") (pintype "output"))
      (node (ref "Q2") (pin "1") (pinfunction "1_1") (pintype "passive"))
    )
    (net (code "55") (name "Net-(ENC-RBIAS)") (class "Default")
      (node (ref "ENC") (pin "14") (pinfunction "RBIAS_14") (pintype "passive"))
      (node (ref "ER10") (pin "1") (pinfunction "1_1") (pintype "passive"))
    )
    (net (code "56") (name "Net-(ENC-RESET)") (class "Default")
      (node (ref "ENC") (pin "10") (pinfunction "RESET_10") (pintype "input"))
      (node (ref "ER1") (pin "1") (pinfunction "1_1") (pintype "passive"))
    )
    (net (code "57") (name "Net-(ENC-TPIN+)") (class "Default")
      (node (ref "ENC") (pin "13") (pinfunction "TPIN+_13") (pintype "input"))
      (node (ref "ERN1") (pin "6") (pinfunction "2_6") (pintype "passive"))
      (node (ref "U$2") (pin "RD+") (pinfunction "RD+_RD+") (pintype "bidirectional"))
    )
    (net (code "58") (name "Net-(ENC-TPIN-)") (class "Default")
      (node (ref "ENC") (pin "12") (pinfunction "TPIN-_12") (pintype "input"))
      (node (ref "ERN1") (pin "5") (pinfunction "2_5") (pintype "passive"))
      (node (ref "U$2") (pin "RD-") (pinfunction "RD-_RD-") (pintype "bidirectional"))
    )
    (net (code "59") (name "Net-(ENC-TPOUT+)") (class "Default")
      (node (ref "ENC") (pin "17") (pinfunction "TPOUT+_17") (pintype "output"))
      (node (ref "ERN1") (pin "1") (pinfunction "1_1") (pintype "passive"))
      (node (ref "U$2") (pin "TD+") (pinfunction "TD+_TD+") (pintype "bidirectional"))
    )
    (net (code "60") (name "Net-(ENC-TPOUT-)") (class "Default")
      (node (ref "ENC") (pin "16") (pinfunction "TPOUT-_16") (pintype "output"))
      (node (ref "ERN1") (pin "2") (pinfunction "1_2") (pintype "passive"))
      (node (ref "U$2") (pin "TD-") (pinfunction "TD-_TD-") (pintype "bidirectional"))
    )
    (net (code "61") (name "Net-(ENC-VCAP)") (class "Default")
      (node (ref "EC3") (pin "+") (pinfunction "+_+") (pintype "passive"))
      (node (ref "ENC") (pin "1") (pinfunction "VCAP_1") (pintype "power_in"))
    )
    (net (code "62") (name "Net-(ERN1A-2)") (class "Default")
      (node (ref "EC4") (pin "1") (pinfunction "1_1") (pintype "passive"))
      (node (ref "EL1") (pin "2") (pinfunction "2_2") (pintype "passive"))
      (node (ref "ERN1") (pin "7") (pinfunction "2_7") (pintype "passive"))
      (node (ref "ERN1") (pin "8") (pinfunction "2_8") (pintype "passive"))
      (node (ref "U$2") (pin "P4") (pinfunction "P4_P4") (pintype "bidirectional"))
    )
    (net (code "63") (name "Net-(ERN1C-1)") (class "Default")
      (node (ref "EC5") (pin "1") (pinfunction "1_1") (pintype "passive"))
      (node (ref "ERN1") (pin "3") (pinfunction "1_3") (pintype "passive"))
      (node (ref "ERN1") (pin "4") (pinfunction "1_4") (pintype "passive"))
      (node (ref "U$2") (pin "P5") (pinfunction "P5_P5") (pintype "bidirectional"))
    )
    (net (code "64") (name "Net-(IC1-A0)") (class "Default")
      (node (ref "IC1") (pin "15") (pinfunction "A0_15") (pintype "input"))
      (node (ref "MR3") (pin "1") (pinfunction "1_1") (pintype "passive"))
    )
    (net (code "65") (name "Net-(IIR1A-2)") (class "Default")
      (node (ref "IIR1") (pin "8") (pinfunction "2_8") (pintype "passive"))
      (node (ref "OK1") (pin "1") (pinfunction "A_1") (pintype "passive"))
    )
    (net (code "66") (name "Net-(IIR1B-1)") (class "Default")
      (node (ref "IIR1") (pin "2") (pinfunction "1_2") (pintype "passive"))
      (node (ref "XI1") (pin "3") (pinfunction "SK_3") (pintype "passive"))
    )
    (net (code "67") (name "Net-(IIR1B-2)") (class "Default")
      (node (ref "IIR1") (pin "7") (pinfunction "2_7") (pintype "passive"))
      (node (ref "OK1") (pin "3") (pinfunction "A_3") (pintype "passive"))
    )
    (net (code "68") (name "Net-(IIR1C-1)") (class "Default")
      (node (ref "IIR1") (pin "3") (pinfunction "1_3") (pintype "passive"))
      (node (ref "XI1") (pin "4") (pinfunction "SK_4") (pintype "passive"))
    )
    (net (code "69") (name "Net-(IIR1C-2)") (class "Default")
      (node (ref "IIR1") (pin "6") (pinfunction "2_6") (pintype "passive"))
      (node (ref "OK1") (pin "5") (pinfunction "A_5") (pintype "passive"))
    )
    (net (code "70") (name "Net-(IIR1D-1)") (class "Default")
      (node (ref "IIR1") (pin "4") (pinfunction "1_4") (pintype "passive"))
      (node (ref "XI1") (pin "5") (pinfunction "SK_5") (pintype "passive"))
    )
    (net (code "71") (name "Net-(IIR1D-2)") (class "Default")
      (node (ref "IIR1") (pin "5") (pinfunction "2_5") (pintype "passive"))
      (node (ref "OK1") (pin "7") (pinfunction "A_7") (pintype "passive"))
    )
    (net (code "72") (name "Net-(IIR2A-2)") (class "Default")
      (node (ref "IIR2") (pin "8") (pinfunction "2_8") (pintype "passive"))
      (node (ref "OK2") (pin "1") (pinfunction "A_1") (pintype "passive"))
    )
    (net (code "73") (name "Net-(IIR2B-1)") (class "Default")
      (node (ref "IIR2") (pin "2") (pinfunction "1_2") (pintype "passive"))
      (node (ref "XI2") (pin "3") (pinfunction "SK_3") (pintype "passive"))
    )
    (net (code "74") (name "Net-(IIR2B-2)") (class "Default")
      (node (ref "IIR2") (pin "7") (pinfunction "2_7") (pintype "passive"))
      (node (ref "OK2") (pin "3") (pinfunction "A_3") (pintype "passive"))
    )
    (net (code "75") (name "Net-(IIR2C-1)") (class "Default")
      (node (ref "IIR2") (pin "3") (pinfunction "1_3") (pintype "passive"))
      (node (ref "XI2") (pin "4") (pinfunction "SK_4") (pintype "passive"))
    )
    (net (code "76") (name "Net-(IIR2C-2)") (class "Default")
      (node (ref "IIR2") (pin "6") (pinfunction "2_6") (pintype "passive"))
      (node (ref "OK2") (pin "5") (pinfunction "A_5") (pintype "passive"))
    )
    (net (code "77") (name "Net-(IIR2D-1)") (class "Default")
      (node (ref "IIR2") (pin "4") (pinfunction "1_4") (pintype "passive"))
      (node (ref "XI2") (pin "5") (pinfunction "SK_5") (pintype "passive"))
    )
    (net (code "78") (name "Net-(IIR2D-2)") (class "Default")
      (node (ref "IIR2") (pin "5") (pinfunction "2_5") (pintype "passive"))
      (node (ref "OK2") (pin "7") (pinfunction "A_7") (pintype "passive"))
    )
    (net (code "79") (name "Net-(INDL-PadA)") (class "Default")
      (node (ref "INDL") (pin "A") (pinfunction "A_A") (pintype "passive"))
      (node (ref "R6") (pin "2") (pinfunction "2_2") (pintype "passive"))
    )
    (net (code "80") (name "Net-(IR3A-2)") (class "Default")
      (node (ref "IL1") (pin "C") (pinfunction "C_C") (pintype "passive"))
      (node (ref "IR3") (pin "8") (pinfunction "2_8") (pintype "passive"))
    )
    (net (code "81") (name "Net-(IR3B-2)") (class "Default")
      (node (ref "IL2") (pin "C") (pinfunction "C_C") (pintype "passive"))
      (node (ref "IR3") (pin "7") (pinfunction "2_7") (pintype "passive"))
    )
    (net (code "82") (name "Net-(IR3C-2)") (class "Default")
      (node (ref "IL3") (pin "C") (pinfunction "C_C") (pintype "passive"))
      (node (ref "IR3") (pin "6") (pinfunction "2_6") (pintype "passive"))
    )
    (net (code "83") (name "Net-(IR3D-2)") (class "Default")
      (node (ref "IL4") (pin "C") (pinfunction "C_C") (pintype "passive"))
      (node (ref "IR3") (pin "5") (pinfunction "2_5") (pintype "passive"))
    )
    (net (code "84") (name "Net-(IR4A-2)") (class "Default")
      (node (ref "IL5") (pin "C") (pinfunction "C_C") (pintype "passive"))
      (node (ref "IR4") (pin "8") (pinfunction "2_8") (pintype "passive"))
    )
    (net (code "85") (name "Net-(IR4B-2)") (class "Default")
      (node (ref "IL6") (pin "C") (pinfunction "C_C") (pintype "passive"))
      (node (ref "IR4") (pin "7") (pinfunction "2_7") (pintype "passive"))
    )
    (net (code "86") (name "Net-(IR4C-2)") (class "Default")
      (node (ref "IL7") (pin "C") (pinfunction "C_C") (pintype "passive"))
      (node (ref "IR4") (pin "6") (pinfunction "2_6") (pintype "passive"))
    )
    (net (code "87") (name "Net-(IR4D-2)") (class "Default")
      (node (ref "IL8") (pin "C") (pinfunction "C_C") (pintype "passive"))
      (node (ref "IR4") (pin "5") (pinfunction "2_5") (pintype "passive"))
    )
    (net (code "88") (name "Net-(MC-PB6(XTAL1{slash}TOSC1))") (class "Default")
      (node (ref "MC") (pin "7") (pinfunction "PB6(XTAL1/TOSC1)_7") (pintype "bidirectional"))
      (node (ref "Q1") (pin "1") (pinfunction "1_1") (pintype "passive"))
    )
    (net (code "89") (name "Net-(MC-PB7(XTAL2{slash}TOSC2))") (class "Default")
      (node (ref "MC") (pin "8") (pinfunction "PB7(XTAL2/TOSC2)_8") (pintype "bidirectional"))
      (node (ref "Q1") (pin "3") (pinfunction "3_3") (pintype "passive"))
    )
    (net (code "90") (name "Net-(OD1-PadC)") (class "Default")
      (node (ref "OD1") (pin "C") (pinfunction "C_C") (pintype "passive"))
      (node (ref "OMF") (pin "2") (pinfunction "2_2") (pintype "bidirectional"))
    )
    (net (code "91") (name "Net-(OK3A-A)") (class "Default")
      (node (ref "OK3") (pin "1") (pinfunction "A_1") (pintype "passive"))
      (node (ref "OR1") (pin "4") (pinfunction "1_4") (pintype "passive"))
    )
    (net (code "92") (name "Net-(OK3A-COL)") (class "Default")
      (node (ref "OK3") (pin "16") (pinfunction "COL_16") (pintype "passive"))
      (node (ref "OR3") (pin "1") (pinfunction "1_1") (pintype "passive"))
    )
    (net (code "93") (name "Net-(OK3B-A)") (class "Default")
      (node (ref "OK3") (pin "3") (pinfunction "A_3") (pintype "passive"))
      (node (ref "OR1") (pin "3") (pinfunction "1_3") (pintype "passive"))
    )
    (net (code "94") (name "Net-(OK3B-COL)") (class "Default")
      (node (ref "OK3") (pin "14") (pinfunction "COL_14") (pintype "passive"))
      (node (ref "OR3") (pin "2") (pinfunction "1_2") (pintype "passive"))
    )
    (net (code "95") (name "Net-(OK3C-A)") (class "Default")
      (node (ref "OK3") (pin "5") (pinfunction "A_5") (pintype "passive"))
      (node (ref "OR1") (pin "2") (pinfunction "1_2") (pintype "passive"))
    )
    (net (code "96") (name "Net-(OK3C-COL)") (class "Default")
      (node (ref "OK3") (pin "12") (pinfunction "COL_12") (pintype "passive"))
      (node (ref "OR3") (pin "3") (pinfunction "1_3") (pintype "passive"))
    )
    (net (code "97") (name "Net-(OK3D-A)") (class "Default")
      (node (ref "OK3") (pin "7") (pinfunction "A_7") (pintype "passive"))
      (node (ref "OR1") (pin "1") (pinfunction "1_1") (pintype "passive"))
    )
    (net (code "98") (name "Net-(OK3D-COL)") (class "Default")
      (node (ref "OK3") (pin "10") (pinfunction "COL_10") (pintype "passive"))
      (node (ref "OR3") (pin "4") (pinfunction "1_4") (pintype "passive"))
    )
    (net (code "99") (name "Net-(OK4A-A)") (class "Default")
      (node (ref "OK4") (pin "1") (pinfunction "A_1") (pintype "passive"))
      (node (ref "OR4") (pin "4") (pinfunction "1_4") (pintype "passive"))
    )
    (net (code "100") (name "Net-(OK4A-COL)") (class "Default")
      (node (ref "OK4") (pin "16") (pinfunction "COL_16") (pintype "passive"))
      (node (ref "OR5") (pin "1") (pinfunction "1_1") (pintype "passive"))
    )
    (net (code "101") (name "Net-(OK4B-A)") (class "Default")
      (node (ref "OK4") (pin "3") (pinfunction "A_3") (pintype "passive"))
      (node (ref "OR4") (pin "3") (pinfunction "1_3") (pintype "passive"))
    )
    (net (code "102") (name "Net-(OK4B-COL)") (class "Default")
      (node (ref "OK4") (pin "14") (pinfunction "COL_14") (pintype "passive"))
      (node (ref "OR5") (pin "2") (pinfunction "1_2") (pintype "passive"))
    )
    (net (code "103") (name "Net-(OK4C-A)") (class "Default")
      (node (ref "OK4") (pin "5") (pinfunction "A_5") (pintype "passive"))
      (node (ref "OR4") (pin "2") (pinfunction "1_2") (pintype "passive"))
    )
    (net (code "104") (name "Net-(OK4C-COL)") (class "Default")
      (node (ref "OK4") (pin "12") (pinfunction "COL_12") (pintype "passive"))
      (node (ref "OR5") (pin "3") (pinfunction "1_3") (pintype "passive"))
    )
    (net (code "105") (name "Net-(OK4D-A)") (class "Default")
      (node (ref "OK4") (pin "7") (pinfunction "A_7") (pintype "passive"))
      (node (ref "OR4") (pin "1") (pinfunction "1_1") (pintype "passive"))
    )
    (net (code "106") (name "Net-(OK4D-COL)") (class "Default")
      (node (ref "OK4") (pin "10") (pinfunction "COL_10") (pintype "passive"))
      (node (ref "OR5") (pin "4") (pinfunction "1_4") (pintype "passive"))
    )
    (net (code "107") (name "Net-(OL4-PadA)") (class "Default")
      (node (ref "OL4") (pin "A") (pinfunction "A_A") (pintype "passive"))
      (node (ref "OR7") (pin "1") (pinfunction "1_1") (pintype "passive"))
    )
    (net (code "108") (name "Net-(OL8-PadA)") (class "Default")
      (node (ref "OL8") (pin "A") (pinfunction "A_A") (pintype "passive"))
      (node (ref "OR8") (pin "1") (pinfunction "1_1") (pintype "passive"))
    )
    (net (code "109") (name "Net-(OR7B-1)") (class "Default")
      (node (ref "OL3") (pin "A") (pinfunction "A_A") (pintype "passive"))
      (node (ref "OR7") (pin "2") (pinfunction "1_2") (pintype "passive"))
    )
    (net (code "110") (name "Net-(OR7C-1)") (class "Default")
      (node (ref "OL2") (pin "A") (pinfunction "A_A") (pintype "passive"))
      (node (ref "OR7") (pin "3") (pinfunction "1_3") (pintype "passive"))
    )
    (net (code "111") (name "Net-(OR7D-1)") (class "Default")
      (node (ref "OL1") (pin "A") (pinfunction "A_A") (pintype "passive"))
      (node (ref "OR7") (pin "4") (pinfunction "1_4") (pintype "passive"))
    )
    (net (code "112") (name "Net-(OR8B-1)") (class "Default")
      (node (ref "OL7") (pin "A") (pinfunction "A_A") (pintype "passive"))
      (node (ref "OR8") (pin "2") (pinfunction "1_2") (pintype "passive"))
    )
    (net (code "113") (name "Net-(OR8C-1)") (class "Default")
      (node (ref "OL6") (pin "A") (pinfunction "A_A") (pintype "passive"))
      (node (ref "OR8") (pin "3") (pinfunction "1_3") (pintype "passive"))
    )
    (net (code "114") (name "Net-(OR8D-1)") (class "Default")
      (node (ref "OL5") (pin "A") (pinfunction "A_A") (pintype "passive"))
      (node (ref "OR8") (pin "4") (pinfunction "1_4") (pintype "passive"))
    )
    (net (code "115") (name "Net-(PD1-PadC)") (class "Default")
      (node (ref "PD1") (pin "C") (pinfunction "C_C") (pintype "passive"))
      (node (ref "PF1") (pin "1") (pinfunction "1_1") (pintype "passive"))
    )
    (net (code "116") (name "Net-(PIC33-OUT)") (class "Default")
      (node (ref "PCO") (pin "P$2") (pinfunction "P$2_P$2") (pintype "passive"))
      (node (ref "PD2") (pin "C") (pinfunction "C_C") (pintype "passive"))
      (node (ref "PIC33") (pin "2") (pinfunction "OUT_2") (pintype "output"))
    )
    (net (code "117") (name "Net-(PL-PadA)") (class "Default")
      (node (ref "PL") (pin "A") (pinfunction "A_A") (pintype "passive"))
      (node (ref "PR1") (pin "1") (pinfunction "1_1") (pintype "passive"))
    )
    (net (code "118") (name "Net-(U1-1C)") (class "Default")
      (node (ref "D1") (pin "2") (pinfunction "2_2") (pintype "bidirectional"))
      (node (ref "OF8") (pin "2") (pinfunction "2_2") (pintype "bidirectional"))
      (node (ref "U1") (pin "18") (pinfunction "1C_18") (pintype "output"))
    )
    (net (code "119") (name "Net-(U1-2C)") (class "Default")
      (node (ref "D1") (pin "1") (pinfunction "1_1") (pintype "bidirectional"))
      (node (ref "OF7") (pin "2") (pinfunction "2_2") (pintype "bidirectional"))
      (node (ref "U1") (pin "17") (pinfunction "2C_17") (pintype "output"))
    )
    (net (code "120") (name "Net-(U1-3C)") (class "Default")
      (node (ref "D2") (pin "2") (pinfunction "2_2") (pintype "bidirectional"))
      (node (ref "OF6") (pin "2") (pinfunction "2_2") (pintype "bidirectional"))
      (node (ref "U1") (pin "16") (pinfunction "3C_16") (pintype "output"))
    )
    (net (code "121") (name "Net-(U1-4C)") (class "Default")
      (node (ref "D2") (pin "1") (pinfunction "1_1") (pintype "bidirectional"))
      (node (ref "OF5") (pin "2") (pinfunction "2_2") (pintype "bidirectional"))
      (node (ref "U1") (pin "15") (pinfunction "4C_15") (pintype "output"))
    )
    (net (code "122") (name "Net-(U1-5C)") (class "Default")
      (node (ref "D3") (pin "2") (pinfunction "2_2") (pintype "bidirectional"))
      (node (ref "OF4") (pin "2") (pinfunction "2_2") (pintype "bidirectional"))
      (node (ref "U1") (pin "14") (pinfunction "5C_14") (pintype "output"))
    )
    (net (code "123") (name "Net-(U1-6C)") (class "Default")
      (node (ref "D3") (pin "1") (pinfunction "1_1") (pintype "bidirectional"))
      (node (ref "OF3") (pin "2") (pinfunction "2_2") (pintype "bidirectional"))
      (node (ref "U1") (pin "13") (pinfunction "6C_13") (pintype "output"))
    )
    (net (code "124") (name "Net-(U1-7C)") (class "Default")
      (node (ref "D4") (pin "2") (pinfunction "2_2") (pintype "bidirectional"))
      (node (ref "OF2") (pin "2") (pinfunction "2_2") (pintype "bidirectional"))
      (node (ref "U1") (pin "12") (pinfunction "7C_12") (pintype "output"))
    )
    (net (code "125") (name "Net-(U1-8C)") (class "Default")
      (node (ref "D4") (pin "1") (pinfunction "1_1") (pintype "bidirectional"))
      (node (ref "OF1") (pin "2") (pinfunction "2_2") (pintype "bidirectional"))
      (node (ref "U1") (pin "11") (pinfunction "8C_11") (pintype "output"))
    )
    (net (code "126") (name "Net-(XI1B-SK)") (class "Default")
      (node (ref "IIR1") (pin "1") (pinfunction "1_1") (pintype "passive"))
      (node (ref "XI1") (pin "2") (pinfunction "SK_2") (pintype "passive"))
    )
    (net (code "127") (name "Net-(XI2B-SK)") (class "Default")
      (node (ref "IIR2") (pin "1") (pinfunction "1_1") (pintype "passive"))
      (node (ref "XI2") (pin "2") (pinfunction "SK_2") (pintype "passive"))
    )
    (net (code "128") (name "Net-(XOA-SK)") (class "Default")
      (node (ref "OD1") (pin "A") (pinfunction "A_A") (pintype "passive"))
      (node (ref "XO") (pin "1") (pinfunction "SK_1") (pintype "passive"))
    )
    (net (code "129") (name "Net-(XOB-SK)") (class "Default")
      (node (ref "OF8") (pin "1") (pinfunction "1_1") (pintype "bidirectional"))
      (node (ref "XO") (pin "10") (pinfunction "SK_10") (pintype "passive"))
    )
    (net (code "130") (name "Net-(XOD-SK)") (class "Default")
      (node (ref "OF1") (pin "1") (pinfunction "1_1") (pintype "bidirectional"))
      (node (ref "XO") (pin "3") (pinfunction "SK_3") (pintype "passive"))
    )
    (net (code "131") (name "Net-(XOE-SK)") (class "Default")
      (node (ref "OF2") (pin "1") (pinfunction "1_1") (pintype "bidirectional"))
      (node (ref "XO") (pin "4") (pinfunction "SK_4") (pintype "passive"))
    )
    (net (code "132") (name "Net-(XOF-SK)") (class "Default")
      (node (ref "OF3") (pin "1") (pinfunction "1_1") (pintype "bidirectional"))
      (node (ref "XO") (pin "5") (pinfunction "SK_5") (pintype "passive"))
    )
    (net (code "133") (name "Net-(XOG-SK)") (class "Default")
      (node (ref "OF4") (pin "1") (pinfunction "1_1") (pintype "bidirectional"))
      (node (ref "XO") (pin "6") (pinfunction "SK_6") (pintype "passive"))
    )
    (net (code "134") (name "Net-(XOH-SK)") (class "Default")
      (node (ref "OF5") (pin "1") (pinfunction "1_1") (pintype "bidirectional"))
      (node (ref "XO") (pin "7") (pinfunction "SK_7") (pintype "passive"))
    )
    (net (code "135") (name "Net-(XOI-SK)") (class "Default")
      (node (ref "OF6") (pin "1") (pinfunction "1_1") (pintype "bidirectional"))
      (node (ref "XO") (pin "8") (pinfunction "SK_8") (pintype "passive"))
    )
    (net (code "136") (name "Net-(XOJ-SK)") (class "Default")
      (node (ref "OF7") (pin "1") (pinfunction "1_1") (pintype "bidirectional"))
      (node (ref "XO") (pin "9") (pinfunction "SK_9") (pintype "passive"))
    )
    (net (code "137") (name "OI1") (class "Default")
      (node (ref "OK3") (pin "15") (pinfunction "EMIT_15") (pintype "passive"))
      (node (ref "OR2") (pin "1") (pinfunction "1_1") (pintype "passive"))
      (node (ref "U1") (pin "8") (pinfunction "8B_8") (pintype "input"))
    )
    (net (code "138") (name "OI2") (class "Default")
      (node (ref "OK3") (pin "13") (pinfunction "EMIT_13") (pintype "passive"))
      (node (ref "OR2") (pin "2") (pinfunction "1_2") (pintype "passive"))
      (node (ref "U1") (pin "7") (pinfunction "7B_7") (pintype "input"))
    )
    (net (code "139") (name "OI3") (class "Default")
      (node (ref "OK3") (pin "11") (pinfunction "EMIT_11") (pintype "passive"))
      (node (ref "OR2") (pin "3") (pinfunction "1_3") (pintype "passive"))
      (node (ref "U1") (pin "6") (pinfunction "6B_6") (pintype "input"))
    )
    (net (code "140") (name "OI4") (class "Default")
      (node (ref "OK3") (pin "9") (pinfunction "EMIT_9") (pintype "passive"))
      (node (ref "OR2") (pin "4") (pinfunction "1_4") (pintype "passive"))
      (node (ref "U1") (pin "5") (pinfunction "5B_5") (pintype "input"))
    )
    (net (code "141") (name "RAW_IV") (class "Default")
      (node (ref "GPIO") (pin "1") (pinfunction "S_1") (pintype "passive"))
      (node (ref "PC1") (pin "+") (pinfunction "+_+") (pintype "passive"))
      (node (ref "PF1") (pin "2") (pinfunction "2_2") (pintype "passive"))
      (node (ref "PIC33") (pin "1") (pinfunction "VIN_1") (pintype "input"))
    )
    (net (code "142") (name "RESET") (class "Default")
      (node (ref "BL") (pin "5") (pinfunction "S_5") (pintype "passive"))
      (node (ref "C2") (pin "1") (pinfunction "1_1") (pintype "passive"))
      (node (ref "MC") (pin "29") (pinfunction "PC6(/RESET)_29") (pintype "bidirectional"))
      (node (ref "R2") (pin "1") (pinfunction "1_1") (pintype "passive"))
      (node (ref "SR") (pin "1") (pinfunction "P_1") (pintype "passive"))
    )
    (net (code "143") (name "RXI") (class "Default")
      (node (ref "MC") (pin "30") (pinfunction "PD0(RXD)_30") (pintype "bidirectional"))
      (node (ref "PP") (pin "4") (pinfunction "S_4") (pintype "passive"))
    )
    (net (code "144") (name "TXO") (class "Default")
      (node (ref "MC") (pin "31") (pinfunction "PD1(TXD)_31") (pintype "bidirectional"))
      (node (ref "PP") (pin "3") (pinfunction "S_3") (pintype "passive"))
    )
    (net (code "145") (name "VDDO") (class "Default")
      (node (ref "D1") (pin "3") (pinfunction "3_3") (pintype "bidirectional"))
      (node (ref "D2") (pin "3") (pinfunction "3_3") (pintype "bidirectional"))
      (node (ref "D3") (pin "3") (pinfunction "3_3") (pintype "bidirectional"))
      (node (ref "D4") (pin "3") (pinfunction "3_3") (pintype "bidirectional"))
      (node (ref "EC6") (pin "+") (pinfunction "+_+") (pintype "passive"))
      (node (ref "OD2") (pin "C") (pinfunction "C_C") (pintype "passive"))
      (node (ref "OMF") (pin "1") (pinfunction "1_1") (pintype "bidirectional"))
      (node (ref "OR3") (pin "5") (pinfunction "2_5") (pintype "passive"))
      (node (ref "OR3") (pin "6") (pinfunction "2_6") (pintype "passive"))
      (node (ref "OR3") (pin "7") (pinfunction "2_7") (pintype "passive"))
      (node (ref "OR3") (pin "8") (pinfunction "2_8") (pintype "passive"))
      (node (ref "OR5") (pin "5") (pinfunction "2_5") (pintype "passive"))
      (node (ref "OR5") (pin "6") (pinfunction "2_6") (pintype "passive"))
      (node (ref "OR5") (pin "7") (pinfunction "2_7") (pintype "passive"))
      (node (ref "OR5") (pin "8") (pinfunction "2_8") (pintype "passive"))
      (node (ref "U1") (pin "10") (pinfunction "COM_10") (pintype "output"))
    )
    (net (code "146") (name "VIN") (class "Default")
      (node (ref "PD1") (pin "A") (pinfunction "A_A") (pintype "passive"))
      (node (ref "PJ1") (pin "VIN0") (pinfunction "PWR_VIN0") (pintype "bidirectional"))
      (node (ref "XV") (pin "2") (pinfunction "SK_2") (pintype "passive"))
    )
    (net (code "147") (name "WFGPIO0") (class "Default")
      (node (ref "GPIO") (pin "13") (pinfunction "S_13") (pintype "passive"))
      (node (ref "WIFI") (pin "GPIO0") (pinfunction "GPIO0_GPIO0") (pintype "bidirectional"))
    )
    (net (code "148") (name "WFGPIO2") (class "Default")
      (node (ref "GPIO") (pin "14") (pinfunction "S_14") (pintype "passive"))
      (node (ref "WIFI") (pin "GPIO2") (pinfunction "GPIO2_GPIO2") (pintype "bidirectional"))
    )
    (net (code "149") (name "unconnected-(ENC-CLKOUT-Pad3)") (class "Default")
      (node (ref "ENC") (pin "3") (pinfunction "CLKOUT_3") (pintype "output"))
    )
    (net (code "150") (name "unconnected-(ENC-WOL-Pad5)") (class "Default")
      (node (ref "ENC") (pin "5") (pinfunction "WOL_5") (pintype "output"))
    )
    (net (code "151") (name "unconnected-(IC1-INTA-Pad20)") (class "Default")
      (node (ref "IC1") (pin "20") (pinfunction "INTA_20") (pintype "output"))
    )
    (net (code "152") (name "unconnected-(PJ1-GND-PadP$4)") (class "Default")
      (node (ref "PJ1") (pin "P$4") (pinfunction "GND_P$4") (pintype "bidirectional"))
    )
    (net (code "153") (name "unconnected-(SHT-PadALERT)") (class "Default")
      (node (ref "SHT") (pin "ALERT") (pinfunction "ALERT_ALERT") (pintype "bidirectional"))
    )
    (net (code "154") (name "unconnected-(SHT-PadRESET)") (class "Default")
      (node (ref "SHT") (pin "RESET") (pinfunction "RESET_RESET") (pintype "bidirectional"))
    )
    (net (code "155") (name "unconnected-(U$2-PadNC)") (class "Default")
      (node (ref "U$2") (pin "NC") (pinfunction "NC_NC") (pintype "bidirectional"))
    )
    (net (code "156") (name "unconnected-(WIFI-PadRST)") (class "Default")
      (node (ref "WIFI") (pin "RST") (pinfunction "RST_RST") (pintype "bidirectional"))
    )
  )
)
